# TakpadV3.net
KiCad netlist of a schematic drawn in EAGLE
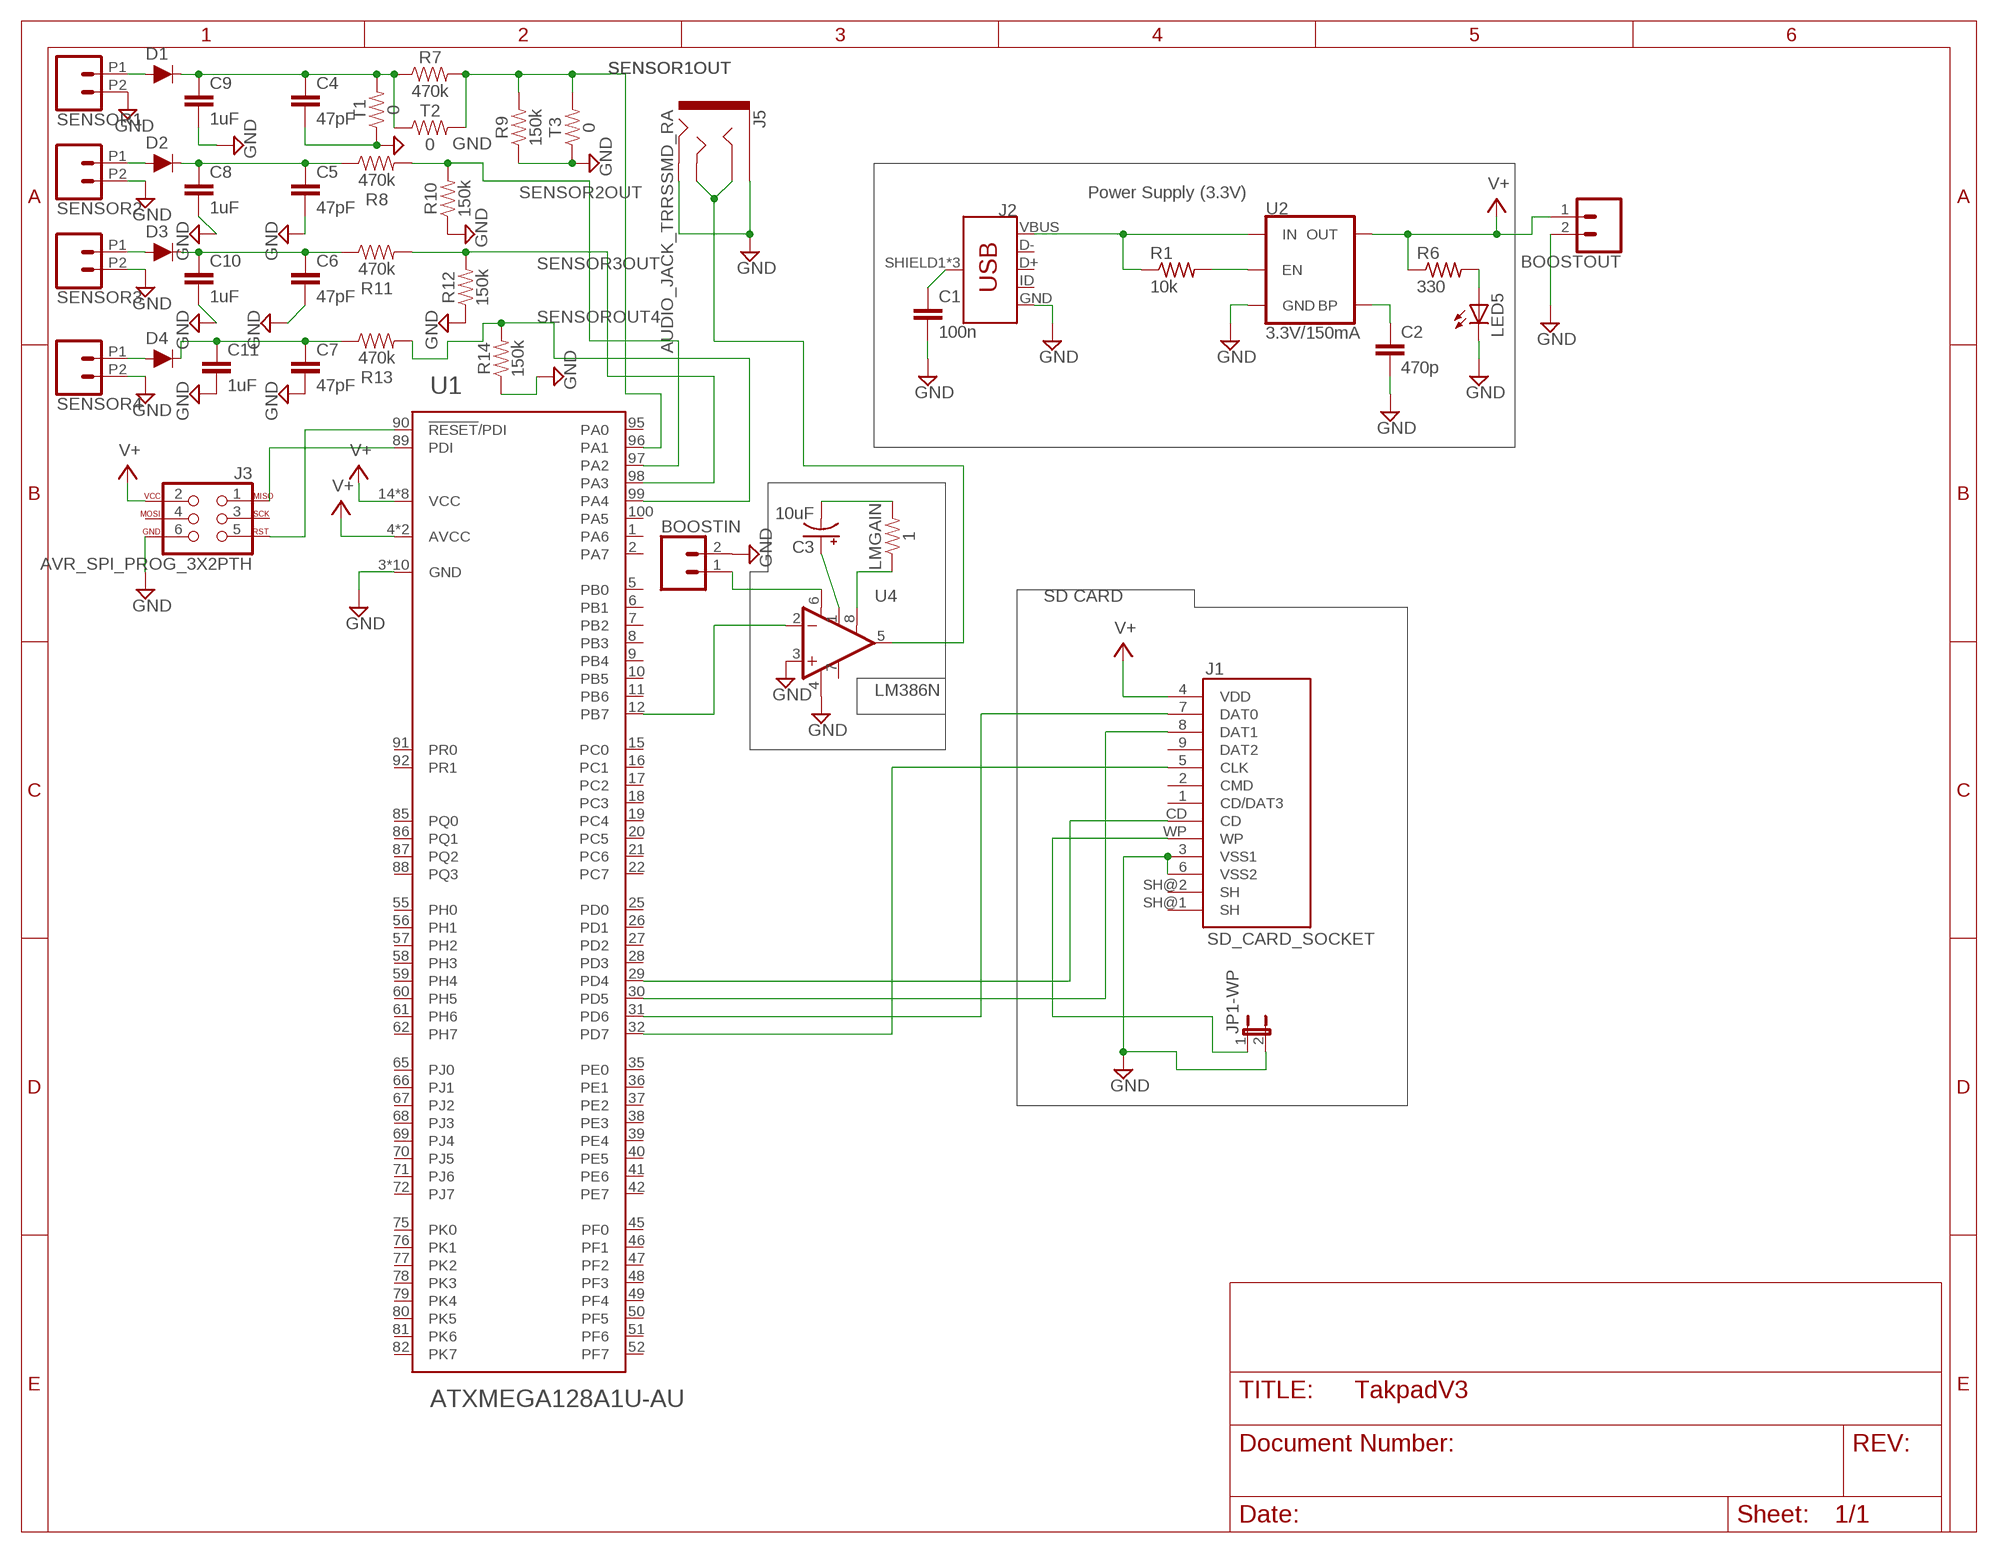
[diagram p0: schematic, sheet 1]

(export (version "E")
  (design (tool "Eeschema 10.0.6"))
  (components
    (comp (ref "BOOSTIN")
      (value "CONN_02")
      (footprint "eagle-import:1X02")
      (libsource (lib "eagle-import") (part "CONN_02"))
    )
    (comp (ref "BOOSTOUT")
      (value "CONN_02")
      (footprint "eagle-import:1X02")
      (libsource (lib "eagle-import") (part "CONN_02"))
    )
    (comp (ref "C1")
      (value "100n")
      (footprint "eagle-import:C1206")
      (libsource (lib "eagle-import") (part "C-EUC1206"))
    )
    (comp (ref "C2")
      (value "470p")
      (footprint "eagle-import:C1206")
      (libsource (lib "eagle-import") (part "C-EUC1206"))
    )
    (comp (ref "C3")
      (value "10uF")
      (footprint "eagle-import:CPOL-RADIAL-2.5MM-5MM-KIT")
      (libsource (lib "eagle-import") (part "10UF-POLAR-RADIAL-2.5MM-KIT-25V-20%"))
    )
    (comp (ref "C4")
      (value "47pF")
      (footprint "eagle-import:0603")
      (libsource (lib "eagle-import") (part "47PF-0603-50V-5%"))
    )
    (comp (ref "C5")
      (value "47pF")
      (footprint "eagle-import:0603")
      (libsource (lib "eagle-import") (part "47PF-0603-50V-5%"))
    )
    (comp (ref "C6")
      (value "47pF")
      (footprint "eagle-import:0603")
      (libsource (lib "eagle-import") (part "47PF-0603-50V-5%"))
    )
    (comp (ref "C7")
      (value "47pF")
      (footprint "eagle-import:0603")
      (libsource (lib "eagle-import") (part "47PF-0603-50V-5%"))
    )
    (comp (ref "C8")
      (value "1uF")
      (footprint "eagle-import:0603")
      (libsource (lib "eagle-import") (part "47PF-0603-50V-5%"))
    )
    (comp (ref "C9")
      (value "1uF")
      (footprint "eagle-import:0603")
      (libsource (lib "eagle-import") (part "47PF-0603-50V-5%"))
    )
    (comp (ref "C10")
      (value "1uF")
      (footprint "eagle-import:0603")
      (libsource (lib "eagle-import") (part "47PF-0603-50V-5%"))
    )
    (comp (ref "C11")
      (value "1uF")
      (footprint "eagle-import:0603")
      (libsource (lib "eagle-import") (part "47PF-0603-50V-5%"))
    )
    (comp (ref "D1")
      (value "200mA/100V/1V")
      (footprint "eagle-import:DIODE-1N4148")
      (libsource (lib "eagle-import") (part "DIODE-1N4148"))
    )
    (comp (ref "D2")
      (value "200mA/100V/1V")
      (footprint "eagle-import:DIODE-1N4148")
      (libsource (lib "eagle-import") (part "DIODE-1N4148"))
    )
    (comp (ref "D3")
      (value "200mA/100V/1V")
      (footprint "eagle-import:DIODE-1N4148")
      (libsource (lib "eagle-import") (part "DIODE-1N4148"))
    )
    (comp (ref "D4")
      (value "200mA/100V/1V")
      (footprint "eagle-import:DIODE-1N4148")
      (libsource (lib "eagle-import") (part "DIODE-1N4148"))
    )
    (comp (ref "J1")
      (value "SD_CARD_SOCKET")
      (footprint "eagle-import:SD")
      (libsource (lib "eagle-import") (part "SD_CARD_SOCKET"))
    )
    (comp (ref "J2")
      (value "USB_MICRO-B_FEMALE-SMT")
      (footprint "eagle-import:USB-B-MICRO-SMD")
      (libsource (lib "eagle-import") (part "USB_MICRO-B_FEMALE-SMT"))
    )
    (comp (ref "J3")
      (value "AVR_SPI_PROG_3X2PTH")
      (footprint "eagle-import:2X3")
      (libsource (lib "eagle-import") (part "AVR_SPI_PROG_3X2PTH"))
    )
    (comp (ref "J5")
      (value "AUDIO_JACK_TRRSSMD_RA")
      (footprint "eagle-import:AUDIO_JACK_3.5MM_TRRS_SMD_RA")
      (fields (field (name "SPICEPREFIX") "E"))
      (libsource (lib "eagle-import") (part "AUDIO_JACK_TRRSSMD_RA"))
    )
    (comp (ref "JP1-WP")
      (value "JUMPER-2PTH")
      (footprint "eagle-import:1X02")
      (libsource (lib "eagle-import") (part "JUMPER-2PTH"))
    )
    (comp (ref "LED5")
      (value "LED10MM")
      (footprint "eagle-import:LED10MM")
      (libsource (lib "eagle-import") (part "LED10MM"))
    )
    (comp (ref "LMGAIN")
      (value "1")
      (footprint "eagle-import:0603")
      (libsource (lib "eagle-import") (part "1OHM-0603-1/10W-1%"))
    )
    (comp (ref "R1")
      (value "10k")
      (footprint "eagle-import:M1206")
      (libsource (lib "eagle-import") (part "R-US_M1206"))
    )
    (comp (ref "R6")
      (value "330")
      (footprint "eagle-import:0204_7")
      (libsource (lib "eagle-import") (part "R-US_0204/7"))
    )
    (comp (ref "R7")
      (value "470k")
      (footprint "eagle-import:AXIAL-0.3")
      (libsource (lib "eagle-import") (part "1KOHM-HORIZ-1/4W-1%"))
    )
    (comp (ref "R8")
      (value "470k")
      (footprint "eagle-import:AXIAL-0.3")
      (libsource (lib "eagle-import") (part "1KOHM-HORIZ-1/4W-1%"))
    )
    (comp (ref "R9")
      (value "150k")
      (footprint "eagle-import:AXIAL-0.3")
      (libsource (lib "eagle-import") (part "1KOHM-HORIZ-1/4W-1%"))
    )
    (comp (ref "R10")
      (value "150k")
      (footprint "eagle-import:AXIAL-0.3")
      (libsource (lib "eagle-import") (part "1KOHM-HORIZ-1/4W-1%"))
    )
    (comp (ref "R11")
      (value "470k")
      (footprint "eagle-import:AXIAL-0.3")
      (libsource (lib "eagle-import") (part "1KOHM-HORIZ-1/4W-1%"))
    )
    (comp (ref "R12")
      (value "150k")
      (footprint "eagle-import:AXIAL-0.3")
      (libsource (lib "eagle-import") (part "1KOHM-HORIZ-1/4W-1%"))
    )
    (comp (ref "R13")
      (value "470k")
      (footprint "eagle-import:AXIAL-0.3")
      (libsource (lib "eagle-import") (part "1KOHM-HORIZ-1/4W-1%"))
    )
    (comp (ref "R14")
      (value "150k")
      (footprint "eagle-import:AXIAL-0.3")
      (libsource (lib "eagle-import") (part "1KOHM-HORIZ-1/4W-1%"))
    )
    (comp (ref "SENSOR1")
      (value "CONN_022.54MM_SCREWTERM")
      (footprint "eagle-import:1X02_2.54_SCREWTERM")
      (libsource (lib "eagle-import") (part "CONN_022.54MM_SCREWTERM"))
    )
    (comp (ref "SENSOR2")
      (value "CONN_022.54MM_SCREWTERM")
      (footprint "eagle-import:1X02_2.54_SCREWTERM")
      (libsource (lib "eagle-import") (part "CONN_022.54MM_SCREWTERM"))
    )
    (comp (ref "SENSOR3")
      (value "CONN_022.54MM_SCREWTERM")
      (footprint "eagle-import:1X02_2.54_SCREWTERM")
      (libsource (lib "eagle-import") (part "CONN_022.54MM_SCREWTERM"))
    )
    (comp (ref "SENSOR4")
      (value "CONN_022.54MM_SCREWTERM")
      (footprint "eagle-import:1X02_2.54_SCREWTERM")
      (libsource (lib "eagle-import") (part "CONN_022.54MM_SCREWTERM"))
    )
    (comp (ref "T1")
      (value "0")
      (footprint "eagle-import:AXIAL-0.3")
      (libsource (lib "eagle-import") (part "1KOHM-HORIZ-1/4W-1%"))
    )
    (comp (ref "T2")
      (value "0")
      (footprint "eagle-import:AXIAL-0.3")
      (libsource (lib "eagle-import") (part "1KOHM-HORIZ-1/4W-1%"))
    )
    (comp (ref "T3")
      (value "0")
      (footprint "eagle-import:AXIAL-0.3")
      (libsource (lib "eagle-import") (part "1KOHM-HORIZ-1/4W-1%"))
    )
    (comp (ref "U1")
      (value "ATXMEGA128A1U-AU")
      (footprint "eagle-import:TQFP-100A-100")
      (libsource (lib "eagle-import") (part "ATXMEGA128A1U-AU"))
    )
    (comp (ref "U2")
      (value "3.3V/150mA")
      (footprint "eagle-import:SOT23-5")
      (libsource (lib "eagle-import") (part "V_REG_MIC52053.3V"))
    )
    (comp (ref "U4")
      (value "LM386N")
      (footprint "eagle-import:DIP08")
      (libsource (lib "eagle-import") (part "LM386"))
    )
  )
  (nets
    (net (code "1") (name "/SENSOR1OUT") (class "Default")
      (node (ref "R7") (pin "P$2") (pinfunction "2_P$2") (pintype "passive"))
      (node (ref "R9") (pin "P$2") (pinfunction "2_P$2") (pintype "passive"))
      (node (ref "T2") (pin "P$2") (pinfunction "2_P$2") (pintype "passive"))
      (node (ref "T3") (pin "P$2") (pinfunction "2_P$2") (pintype "passive"))
      (node (ref "U1") (pin "96") (pinfunction "PA1_96") (pintype "bidirectional"))
    )
    (net (code "2") (name "/SENSOR2OUT") (class "Default")
      (node (ref "R10") (pin "P$2") (pinfunction "2_P$2") (pintype "passive"))
      (node (ref "R8") (pin "P$2") (pinfunction "2_P$2") (pintype "passive"))
      (node (ref "U1") (pin "97") (pinfunction "PA2_97") (pintype "bidirectional"))
    )
    (net (code "3") (name "/SENSOR3OUT") (class "Default")
      (node (ref "R11") (pin "P$2") (pinfunction "2_P$2") (pintype "passive"))
      (node (ref "R12") (pin "P$2") (pinfunction "2_P$2") (pintype "passive"))
      (node (ref "U1") (pin "98") (pinfunction "PA3_98") (pintype "bidirectional"))
    )
    (net (code "4") (name "/SENSOROUT4") (class "Default")
      (node (ref "R13") (pin "P$2") (pinfunction "2_P$2") (pintype "passive"))
      (node (ref "R14") (pin "P$2") (pinfunction "2_P$2") (pintype "passive"))
      (node (ref "U1") (pin "99") (pinfunction "PA4_99") (pintype "bidirectional"))
    )
    (net (code "5") (name "GND") (class "Default")
      (node (ref "BOOSTIN") (pin "2") (pinfunction "2_2") (pintype "passive"))
      (node (ref "BOOSTOUT") (pin "2") (pinfunction "2_2") (pintype "passive"))
      (node (ref "C1") (pin "2") (pinfunction "2_2") (pintype "passive"))
      (node (ref "C10") (pin "2") (pinfunction "2_2") (pintype "passive"))
      (node (ref "C11") (pin "2") (pinfunction "2_2") (pintype "passive"))
      (node (ref "C2") (pin "2") (pinfunction "2_2") (pintype "passive"))
      (node (ref "C4") (pin "2") (pinfunction "2_2") (pintype "passive"))
      (node (ref "C5") (pin "2") (pinfunction "2_2") (pintype "passive"))
      (node (ref "C6") (pin "2") (pinfunction "2_2") (pintype "passive"))
      (node (ref "C7") (pin "2") (pinfunction "2_2") (pintype "passive"))
      (node (ref "C8") (pin "2") (pinfunction "2_2") (pintype "passive"))
      (node (ref "C9") (pin "2") (pinfunction "2_2") (pintype "passive"))
      (node (ref "J1") (pin "3") (pinfunction "VSS1_3") (pintype "power_in"))
      (node (ref "J1") (pin "6") (pinfunction "VSS2_6") (pintype "power_in"))
      (node (ref "J2") (pin "GND") (pinfunction "GND_GND") (pintype "power_in"))
      (node (ref "J3") (pin "6") (pinfunction "6_6") (pintype "passive"))
      (node (ref "J5") (pin "EARTH") (pinfunction "EARTH_EARTH") (pintype "bidirectional"))
      (node (ref "J5") (pin "RING2") (pinfunction "RING2_RING2") (pintype "bidirectional"))
      (node (ref "JP1-WP") (pin "2") (pinfunction "2_2") (pintype "passive"))
      (node (ref "LED5") (pin "K") (pinfunction "C_K") (pintype "passive"))
      (node (ref "R10") (pin "P$1") (pinfunction "1_P$1") (pintype "passive"))
      (node (ref "R12") (pin "P$1") (pinfunction "1_P$1") (pintype "passive"))
      (node (ref "R14") (pin "P$1") (pinfunction "1_P$1") (pintype "passive"))
      (node (ref "R9") (pin "P$1") (pinfunction "1_P$1") (pintype "passive"))
      (node (ref "SENSOR1") (pin "P2") (pinfunction "2_P2") (pintype "passive"))
      (node (ref "SENSOR2") (pin "P2") (pinfunction "2_P2") (pintype "passive"))
      (node (ref "SENSOR3") (pin "P2") (pinfunction "2_P2") (pintype "passive"))
      (node (ref "SENSOR4") (pin "P2") (pinfunction "2_P2") (pintype "passive"))
      (node (ref "T1") (pin "P$1") (pinfunction "1_P$1") (pintype "passive"))
      (node (ref "T3") (pin "P$1") (pinfunction "1_P$1") (pintype "passive"))
      (node (ref "U1") (pin "13") (pinfunction "GND_13") (pintype "power_in"))
      (node (ref "U1") (pin "23") (pinfunction "GND_23") (pintype "power_in"))
      (node (ref "U1") (pin "3") (pinfunction "GND_3") (pintype "power_in"))
      (node (ref "U1") (pin "33") (pinfunction "GND_33") (pintype "power_in"))
      (node (ref "U1") (pin "43") (pinfunction "GND_43") (pintype "power_in"))
      (node (ref "U1") (pin "53") (pinfunction "GND_53") (pintype "power_in"))
      (node (ref "U1") (pin "63") (pinfunction "GND_63") (pintype "power_in"))
      (node (ref "U1") (pin "73") (pinfunction "GND_73") (pintype "power_in"))
      (node (ref "U1") (pin "84") (pinfunction "GND_84") (pintype "power_in"))
      (node (ref "U1") (pin "93") (pinfunction "GND_93") (pintype "power_in"))
      (node (ref "U2") (pin "2") (pinfunction "GND_2") (pintype "input"))
      (node (ref "U4") (pin "3") (pinfunction "+IN_3") (pintype "input"))
      (node (ref "U4") (pin "4") (pinfunction "V-_4") (pintype "power_in"))
    )
    (net (code "6") (name "Net-(C1-Pad1)") (class "Default")
      (node (ref "C1") (pin "1") (pinfunction "1_1") (pintype "passive"))
      (node (ref "J2") (pin "SHIELD1") (pinfunction "SHIELD_SHIELD1") (pintype "bidirectional"))
      (node (ref "J2") (pin "SHIELD2") (pinfunction "SHIELD_SHIELD2") (pintype "bidirectional"))
      (node (ref "J2") (pin "SHIELD3") (pinfunction "SHIELD_SHIELD3") (pintype "bidirectional"))
    )
    (net (code "7") (name "Net-(C3-+)") (class "Default")
      (node (ref "C3") (pin "1") (pinfunction "+_1") (pintype "passive"))
      (node (ref "U4") (pin "1") (pinfunction "GAIN_1") (pintype "bidirectional"))
    )
    (net (code "8") (name "Net-(C3--)") (class "Default")
      (node (ref "C3") (pin "2") (pinfunction "-_2") (pintype "passive"))
      (node (ref "LMGAIN") (pin "2") (pinfunction "2_2") (pintype "passive"))
    )
    (net (code "9") (name "Net-(J1-CLK)") (class "Default")
      (node (ref "J1") (pin "5") (pinfunction "CLK_5") (pintype "bidirectional"))
      (node (ref "U1") (pin "32") (pinfunction "PD7_32") (pintype "bidirectional"))
    )
    (net (code "10") (name "Net-(J1-DAT0)") (class "Default")
      (node (ref "J1") (pin "7") (pinfunction "DAT0_7") (pintype "bidirectional"))
      (node (ref "U1") (pin "31") (pinfunction "PD6_31") (pintype "bidirectional"))
    )
    (net (code "11") (name "Net-(J1-DAT1)") (class "Default")
      (node (ref "J1") (pin "8") (pinfunction "DAT1_8") (pintype "bidirectional"))
      (node (ref "U1") (pin "30") (pinfunction "PD5_30") (pintype "bidirectional"))
    )
    (net (code "12") (name "Net-(J1-PadWP)") (class "Default")
      (node (ref "J1") (pin "WP") (pinfunction "WP_WP") (pintype "bidirectional"))
      (node (ref "JP1-WP") (pin "1") (pinfunction "1_1") (pintype "passive"))
    )
    (net (code "13") (name "Net-(LED5-PadA)") (class "Default")
      (node (ref "LED5") (pin "A") (pinfunction "A_A") (pintype "passive"))
      (node (ref "R6") (pin "2") (pinfunction "2_2") (pintype "passive"))
    )
    (net (code "14") (name "Net-(LMGAIN-Pad1)") (class "Default")
      (node (ref "LMGAIN") (pin "1") (pinfunction "1_1") (pintype "passive"))
      (node (ref "U4") (pin "8") (pinfunction "GAIN_8") (pintype "bidirectional"))
    )
    (net (code "15") (name "Net-(R7-1)") (class "Default")
      (node (ref "C4") (pin "1") (pinfunction "1_1") (pintype "passive"))
      (node (ref "C9") (pin "1") (pinfunction "1_1") (pintype "passive"))
      (node (ref "D1") (pin "C") (pinfunction "C_C") (pintype "passive"))
      (node (ref "R7") (pin "P$1") (pinfunction "1_P$1") (pintype "passive"))
      (node (ref "T1") (pin "P$2") (pinfunction "2_P$2") (pintype "passive"))
      (node (ref "T2") (pin "P$1") (pinfunction "1_P$1") (pintype "passive"))
    )
    (net (code "16") (name "Net-(R8-1)") (class "Default")
      (node (ref "C5") (pin "1") (pinfunction "1_1") (pintype "passive"))
      (node (ref "C8") (pin "1") (pinfunction "1_1") (pintype "passive"))
      (node (ref "D2") (pin "C") (pinfunction "C_C") (pintype "passive"))
      (node (ref "R8") (pin "P$1") (pinfunction "1_P$1") (pintype "passive"))
    )
    (net (code "17") (name "Net-(R11-1)") (class "Default")
      (node (ref "C10") (pin "1") (pinfunction "1_1") (pintype "passive"))
      (node (ref "C6") (pin "1") (pinfunction "1_1") (pintype "passive"))
      (node (ref "D3") (pin "C") (pinfunction "C_C") (pintype "passive"))
      (node (ref "R11") (pin "P$1") (pinfunction "1_P$1") (pintype "passive"))
    )
    (net (code "18") (name "Net-(R13-1)") (class "Default")
      (node (ref "C11") (pin "1") (pinfunction "1_1") (pintype "passive"))
      (node (ref "C7") (pin "1") (pinfunction "1_1") (pintype "passive"))
      (node (ref "D4") (pin "C") (pinfunction "C_C") (pintype "passive"))
      (node (ref "R13") (pin "P$1") (pinfunction "1_P$1") (pintype "passive"))
    )
    (net (code "19") (name "Net-(SENSOR1-1)") (class "Default")
      (node (ref "D1") (pin "A") (pinfunction "A_A") (pintype "passive"))
      (node (ref "SENSOR1") (pin "P1") (pinfunction "1_P1") (pintype "passive"))
    )
    (net (code "20") (name "Net-(SENSOR2-1)") (class "Default")
      (node (ref "D2") (pin "A") (pinfunction "A_A") (pintype "passive"))
      (node (ref "SENSOR2") (pin "P1") (pinfunction "1_P1") (pintype "passive"))
    )
    (net (code "21") (name "Net-(SENSOR3-1)") (class "Default")
      (node (ref "D3") (pin "A") (pinfunction "A_A") (pintype "passive"))
      (node (ref "SENSOR3") (pin "P1") (pinfunction "1_P1") (pintype "passive"))
    )
    (net (code "22") (name "Net-(SENSOR4-1)") (class "Default")
      (node (ref "D4") (pin "A") (pinfunction "A_A") (pintype "passive"))
      (node (ref "SENSOR4") (pin "P1") (pinfunction "1_P1") (pintype "passive"))
    )
    (net (code "23") (name "Net-(U1-PB7)") (class "Default")
      (node (ref "U1") (pin "12") (pinfunction "PB7_12") (pintype "bidirectional"))
      (node (ref "U4") (pin "2") (pinfunction "-IN_2") (pintype "input"))
    )
    (net (code "24") (name "Net-(U1-PD4)") (class "Default")
      (node (ref "J1") (pin "CD") (pinfunction "CD_CD") (pintype "bidirectional"))
      (node (ref "U1") (pin "29") (pinfunction "PD4_29") (pintype "bidirectional"))
    )
    (net (code "25") (name "Net-(U1-PDI)") (class "Default")
      (node (ref "J3") (pin "1") (pinfunction "1_1") (pintype "passive"))
      (node (ref "U1") (pin "89") (pinfunction "PDI_89") (pintype "bidirectional"))
    )
    (net (code "26") (name "Net-(U1-~{RESET}{slash}PDI)") (class "Default")
      (node (ref "J3") (pin "5") (pinfunction "5_5") (pintype "passive"))
      (node (ref "U1") (pin "90") (pinfunction "~{RESET}/PDI_90") (pintype "bidirectional"))
    )
    (net (code "27") (name "Net-(U2-BP)") (class "Default")
      (node (ref "C2") (pin "1") (pinfunction "1_1") (pintype "passive"))
      (node (ref "U2") (pin "4") (pinfunction "BP_4") (pintype "input"))
    )
    (net (code "28") (name "Net-(U2-EN)") (class "Default")
      (node (ref "R1") (pin "2") (pinfunction "2_2") (pintype "passive"))
      (node (ref "U2") (pin "3") (pinfunction "EN_3") (pintype "input"))
    )
    (net (code "29") (name "Net-(U2-IN)") (class "Default")
      (node (ref "J2") (pin "VBUS") (pinfunction "VBUS_VBUS") (pintype "power_in"))
      (node (ref "R1") (pin "1") (pinfunction "1_1") (pintype "passive"))
      (node (ref "U2") (pin "1") (pinfunction "IN_1") (pintype "input"))
    )
    (net (code "30") (name "Net-(U4-OUT)") (class "Default")
      (node (ref "J5") (pin "RING1") (pinfunction "RING1_RING1") (pintype "bidirectional"))
      (node (ref "J5") (pin "TIP") (pinfunction "TIP_TIP") (pintype "bidirectional"))
      (node (ref "U4") (pin "5") (pinfunction "OUT_5") (pintype "output"))
    )
    (net (code "31") (name "Net-(U4-V+)") (class "Default")
      (node (ref "BOOSTIN") (pin "1") (pinfunction "1_1") (pintype "passive"))
      (node (ref "U4") (pin "6") (pinfunction "V+_6") (pintype "power_in"))
    )
    (net (code "32") (name "V+") (class "Default")
      (node (ref "BOOSTOUT") (pin "1") (pinfunction "1_1") (pintype "passive"))
      (node (ref "J1") (pin "4") (pinfunction "VDD_4") (pintype "power_in"))
      (node (ref "J3") (pin "2") (pinfunction "2_2") (pintype "passive"))
      (node (ref "R6") (pin "1") (pinfunction "1_1") (pintype "passive"))
      (node (ref "U1") (pin "14") (pinfunction "VCC_14") (pintype "power_in"))
      (node (ref "U1") (pin "24") (pinfunction "VCC_24") (pintype "power_in"))
      (node (ref "U1") (pin "34") (pinfunction "VCC_34") (pintype "power_in"))
      (node (ref "U1") (pin "4") (pinfunction "AVCC_4") (pintype "power_in"))
      (node (ref "U1") (pin "44") (pinfunction "VCC_44") (pintype "power_in"))
      (node (ref "U1") (pin "54") (pinfunction "VCC_54") (pintype "power_in"))
      (node (ref "U1") (pin "64") (pinfunction "VCC_64") (pintype "power_in"))
      (node (ref "U1") (pin "74") (pinfunction "VCC_74") (pintype "power_in"))
      (node (ref "U1") (pin "83") (pinfunction "VCC_83") (pintype "power_in"))
      (node (ref "U1") (pin "94") (pinfunction "AVCC_94") (pintype "power_in"))
      (node (ref "U2") (pin "5") (pinfunction "OUT_5") (pintype "passive"))
    )
    (net (code "33") (name "unconnected-(J1-CD{slash}DAT3-Pad1)") (class "Default")
      (node (ref "J1") (pin "1") (pinfunction "CD/DAT3_1") (pintype "bidirectional"))
    )
    (net (code "34") (name "unconnected-(J1-CMD-Pad2)") (class "Default")
      (node (ref "J1") (pin "2") (pinfunction "CMD_2") (pintype "bidirectional"))
    )
    (net (code "35") (name "unconnected-(J1-DAT2-Pad9)") (class "Default")
      (node (ref "J1") (pin "9") (pinfunction "DAT2_9") (pintype "bidirectional"))
    )
    (net (code "36") (name "unconnected-(J1-SH-PadSH@1)") (class "Default")
      (node (ref "J1") (pin "SH@1") (pinfunction "SH_SH@1") (pintype "bidirectional"))
    )
    (net (code "37") (name "unconnected-(J1-SH-PadSH@2)") (class "Default")
      (node (ref "J1") (pin "SH@2") (pinfunction "SH_SH@2") (pintype "bidirectional"))
    )
    (net (code "38") (name "unconnected-(J2-PadD+)") (class "Default")
      (node (ref "J2") (pin "D+") (pinfunction "D+_D+") (pintype "bidirectional"))
    )
    (net (code "39") (name "unconnected-(J2-PadD-)") (class "Default")
      (node (ref "J2") (pin "D-") (pinfunction "D-_D-") (pintype "bidirectional"))
    )
    (net (code "40") (name "unconnected-(J2-PadID)") (class "Default")
      (node (ref "J2") (pin "ID") (pinfunction "ID_ID") (pintype "bidirectional"))
    )
    (net (code "41") (name "unconnected-(J3-Pad3)") (class "Default")
      (node (ref "J3") (pin "3") (pinfunction "3_3") (pintype "passive"))
    )
    (net (code "42") (name "unconnected-(J3-Pad4)") (class "Default")
      (node (ref "J3") (pin "4") (pinfunction "4_4") (pintype "passive"))
    )
    (net (code "43") (name "unconnected-(U1-PA0-Pad95)") (class "Default")
      (node (ref "U1") (pin "95") (pinfunction "PA0_95") (pintype "bidirectional"))
    )
    (net (code "44") (name "unconnected-(U1-PA5-Pad100)") (class "Default")
      (node (ref "U1") (pin "100") (pinfunction "PA5_100") (pintype "bidirectional"))
    )
    (net (code "45") (name "unconnected-(U1-PA6-Pad1)") (class "Default")
      (node (ref "U1") (pin "1") (pinfunction "PA6_1") (pintype "bidirectional"))
    )
    (net (code "46") (name "unconnected-(U1-PA7-Pad2)") (class "Default")
      (node (ref "U1") (pin "2") (pinfunction "PA7_2") (pintype "bidirectional"))
    )
    (net (code "47") (name "unconnected-(U1-PB0-Pad5)") (class "Default")
      (node (ref "U1") (pin "5") (pinfunction "PB0_5") (pintype "bidirectional"))
    )
    (net (code "48") (name "unconnected-(U1-PB1-Pad6)") (class "Default")
      (node (ref "U1") (pin "6") (pinfunction "PB1_6") (pintype "bidirectional"))
    )
    (net (code "49") (name "unconnected-(U1-PB2-Pad7)") (class "Default")
      (node (ref "U1") (pin "7") (pinfunction "PB2_7") (pintype "bidirectional"))
    )
    (net (code "50") (name "unconnected-(U1-PB3-Pad8)") (class "Default")
      (node (ref "U1") (pin "8") (pinfunction "PB3_8") (pintype "bidirectional"))
    )
    (net (code "51") (name "unconnected-(U1-PB4-Pad9)") (class "Default")
      (node (ref "U1") (pin "9") (pinfunction "PB4_9") (pintype "bidirectional"))
    )
    (net (code "52") (name "unconnected-(U1-PB5-Pad10)") (class "Default")
      (node (ref "U1") (pin "10") (pinfunction "PB5_10") (pintype "bidirectional"))
    )
    (net (code "53") (name "unconnected-(U1-PB6-Pad11)") (class "Default")
      (node (ref "U1") (pin "11") (pinfunction "PB6_11") (pintype "bidirectional"))
    )
    (net (code "54") (name "unconnected-(U1-PC0-Pad15)") (class "Default")
      (node (ref "U1") (pin "15") (pinfunction "PC0_15") (pintype "bidirectional"))
    )
    (net (code "55") (name "unconnected-(U1-PC1-Pad16)") (class "Default")
      (node (ref "U1") (pin "16") (pinfunction "PC1_16") (pintype "bidirectional"))
    )
    (net (code "56") (name "unconnected-(U1-PC2-Pad17)") (class "Default")
      (node (ref "U1") (pin "17") (pinfunction "PC2_17") (pintype "bidirectional"))
    )
    (net (code "57") (name "unconnected-(U1-PC3-Pad18)") (class "Default")
      (node (ref "U1") (pin "18") (pinfunction "PC3_18") (pintype "bidirectional"))
    )
    (net (code "58") (name "unconnected-(U1-PC4-Pad19)") (class "Default")
      (node (ref "U1") (pin "19") (pinfunction "PC4_19") (pintype "bidirectional"))
    )
    (net (code "59") (name "unconnected-(U1-PC5-Pad20)") (class "Default")
      (node (ref "U1") (pin "20") (pinfunction "PC5_20") (pintype "bidirectional"))
    )
    (net (code "60") (name "unconnected-(U1-PC6-Pad21)") (class "Default")
      (node (ref "U1") (pin "21") (pinfunction "PC6_21") (pintype "bidirectional"))
    )
    (net (code "61") (name "unconnected-(U1-PC7-Pad22)") (class "Default")
      (node (ref "U1") (pin "22") (pinfunction "PC7_22") (pintype "bidirectional"))
    )
    (net (code "62") (name "unconnected-(U1-PD0-Pad25)") (class "Default")
      (node (ref "U1") (pin "25") (pinfunction "PD0_25") (pintype "bidirectional"))
    )
    (net (code "63") (name "unconnected-(U1-PD1-Pad26)") (class "Default")
      (node (ref "U1") (pin "26") (pinfunction "PD1_26") (pintype "bidirectional"))
    )
    (net (code "64") (name "unconnected-(U1-PD2-Pad27)") (class "Default")
      (node (ref "U1") (pin "27") (pinfunction "PD2_27") (pintype "bidirectional"))
    )
    (net (code "65") (name "unconnected-(U1-PD3-Pad28)") (class "Default")
      (node (ref "U1") (pin "28") (pinfunction "PD3_28") (pintype "bidirectional"))
    )
    (net (code "66") (name "unconnected-(U1-PE0-Pad35)") (class "Default")
      (node (ref "U1") (pin "35") (pinfunction "PE0_35") (pintype "bidirectional"))
    )
    (net (code "67") (name "unconnected-(U1-PE1-Pad36)") (class "Default")
      (node (ref "U1") (pin "36") (pinfunction "PE1_36") (pintype "bidirectional"))
    )
    (net (code "68") (name "unconnected-(U1-PE2-Pad37)") (class "Default")
      (node (ref "U1") (pin "37") (pinfunction "PE2_37") (pintype "bidirectional"))
    )
    (net (code "69") (name "unconnected-(U1-PE3-Pad38)") (class "Default")
      (node (ref "U1") (pin "38") (pinfunction "PE3_38") (pintype "bidirectional"))
    )
    (net (code "70") (name "unconnected-(U1-PE4-Pad39)") (class "Default")
      (node (ref "U1") (pin "39") (pinfunction "PE4_39") (pintype "bidirectional"))
    )
    (net (code "71") (name "unconnected-(U1-PE5-Pad40)") (class "Default")
      (node (ref "U1") (pin "40") (pinfunction "PE5_40") (pintype "bidirectional"))
    )
    (net (code "72") (name "unconnected-(U1-PE6-Pad41)") (class "Default")
      (node (ref "U1") (pin "41") (pinfunction "PE6_41") (pintype "bidirectional"))
    )
    (net (code "73") (name "unconnected-(U1-PE7-Pad42)") (class "Default")
      (node (ref "U1") (pin "42") (pinfunction "PE7_42") (pintype "bidirectional"))
    )
    (net (code "74") (name "unconnected-(U1-PF0-Pad45)") (class "Default")
      (node (ref "U1") (pin "45") (pinfunction "PF0_45") (pintype "bidirectional"))
    )
    (net (code "75") (name "unconnected-(U1-PF1-Pad46)") (class "Default")
      (node (ref "U1") (pin "46") (pinfunction "PF1_46") (pintype "bidirectional"))
    )
    (net (code "76") (name "unconnected-(U1-PF2-Pad47)") (class "Default")
      (node (ref "U1") (pin "47") (pinfunction "PF2_47") (pintype "bidirectional"))
    )
    (net (code "77") (name "unconnected-(U1-PF3-Pad48)") (class "Default")
      (node (ref "U1") (pin "48") (pinfunction "PF3_48") (pintype "bidirectional"))
    )
    (net (code "78") (name "unconnected-(U1-PF4-Pad49)") (class "Default")
      (node (ref "U1") (pin "49") (pinfunction "PF4_49") (pintype "bidirectional"))
    )
    (net (code "79") (name "unconnected-(U1-PF5-Pad50)") (class "Default")
      (node (ref "U1") (pin "50") (pinfunction "PF5_50") (pintype "bidirectional"))
    )
    (net (code "80") (name "unconnected-(U1-PF6-Pad51)") (class "Default")
      (node (ref "U1") (pin "51") (pinfunction "PF6_51") (pintype "bidirectional"))
    )
    (net (code "81") (name "unconnected-(U1-PF7-Pad52)") (class "Default")
      (node (ref "U1") (pin "52") (pinfunction "PF7_52") (pintype "bidirectional"))
    )
    (net (code "82") (name "unconnected-(U1-PH0-Pad55)") (class "Default")
      (node (ref "U1") (pin "55") (pinfunction "PH0_55") (pintype "bidirectional"))
    )
    (net (code "83") (name "unconnected-(U1-PH1-Pad56)") (class "Default")
      (node (ref "U1") (pin "56") (pinfunction "PH1_56") (pintype "bidirectional"))
    )
    (net (code "84") (name "unconnected-(U1-PH2-Pad57)") (class "Default")
      (node (ref "U1") (pin "57") (pinfunction "PH2_57") (pintype "bidirectional"))
    )
    (net (code "85") (name "unconnected-(U1-PH3-Pad58)") (class "Default")
      (node (ref "U1") (pin "58") (pinfunction "PH3_58") (pintype "bidirectional"))
    )
    (net (code "86") (name "unconnected-(U1-PH4-Pad59)") (class "Default")
      (node (ref "U1") (pin "59") (pinfunction "PH4_59") (pintype "bidirectional"))
    )
    (net (code "87") (name "unconnected-(U1-PH5-Pad60)") (class "Default")
      (node (ref "U1") (pin "60") (pinfunction "PH5_60") (pintype "bidirectional"))
    )
    (net (code "88") (name "unconnected-(U1-PH6-Pad61)") (class "Default")
      (node (ref "U1") (pin "61") (pinfunction "PH6_61") (pintype "bidirectional"))
    )
    (net (code "89") (name "unconnected-(U1-PH7-Pad62)") (class "Default")
      (node (ref "U1") (pin "62") (pinfunction "PH7_62") (pintype "bidirectional"))
    )
    (net (code "90") (name "unconnected-(U1-PJ0-Pad65)") (class "Default")
      (node (ref "U1") (pin "65") (pinfunction "PJ0_65") (pintype "bidirectional"))
    )
    (net (code "91") (name "unconnected-(U1-PJ1-Pad66)") (class "Default")
      (node (ref "U1") (pin "66") (pinfunction "PJ1_66") (pintype "bidirectional"))
    )
    (net (code "92") (name "unconnected-(U1-PJ2-Pad67)") (class "Default")
      (node (ref "U1") (pin "67") (pinfunction "PJ2_67") (pintype "bidirectional"))
    )
    (net (code "93") (name "unconnected-(U1-PJ3-Pad68)") (class "Default")
      (node (ref "U1") (pin "68") (pinfunction "PJ3_68") (pintype "bidirectional"))
    )
    (net (code "94") (name "unconnected-(U1-PJ4-Pad69)") (class "Default")
      (node (ref "U1") (pin "69") (pinfunction "PJ4_69") (pintype "bidirectional"))
    )
    (net (code "95") (name "unconnected-(U1-PJ5-Pad70)") (class "Default")
      (node (ref "U1") (pin "70") (pinfunction "PJ5_70") (pintype "bidirectional"))
    )
    (net (code "96") (name "unconnected-(U1-PJ6-Pad71)") (class "Default")
      (node (ref "U1") (pin "71") (pinfunction "PJ6_71") (pintype "bidirectional"))
    )
    (net (code "97") (name "unconnected-(U1-PJ7-Pad72)") (class "Default")
      (node (ref "U1") (pin "72") (pinfunction "PJ7_72") (pintype "bidirectional"))
    )
    (net (code "98") (name "unconnected-(U1-PK0-Pad75)") (class "Default")
      (node (ref "U1") (pin "75") (pinfunction "PK0_75") (pintype "bidirectional"))
    )
    (net (code "99") (name "unconnected-(U1-PK1-Pad76)") (class "Default")
      (node (ref "U1") (pin "76") (pinfunction "PK1_76") (pintype "bidirectional"))
    )
    (net (code "100") (name "unconnected-(U1-PK2-Pad77)") (class "Default")
      (node (ref "U1") (pin "77") (pinfunction "PK2_77") (pintype "bidirectional"))
    )
    (net (code "101") (name "unconnected-(U1-PK3-Pad78)") (class "Default")
      (node (ref "U1") (pin "78") (pinfunction "PK3_78") (pintype "bidirectional"))
    )
    (net (code "102") (name "unconnected-(U1-PK4-Pad79)") (class "Default")
      (node (ref "U1") (pin "79") (pinfunction "PK4_79") (pintype "bidirectional"))
    )
    (net (code "103") (name "unconnected-(U1-PK5-Pad80)") (class "Default")
      (node (ref "U1") (pin "80") (pinfunction "PK5_80") (pintype "bidirectional"))
    )
    (net (code "104") (name "unconnected-(U1-PK6-Pad81)") (class "Default")
      (node (ref "U1") (pin "81") (pinfunction "PK6_81") (pintype "bidirectional"))
    )
    (net (code "105") (name "unconnected-(U1-PK7-Pad82)") (class "Default")
      (node (ref "U1") (pin "82") (pinfunction "PK7_82") (pintype "bidirectional"))
    )
    (net (code "106") (name "unconnected-(U1-PQ0-Pad85)") (class "Default")
      (node (ref "U1") (pin "85") (pinfunction "PQ0_85") (pintype "bidirectional"))
    )
    (net (code "107") (name "unconnected-(U1-PQ1-Pad86)") (class "Default")
      (node (ref "U1") (pin "86") (pinfunction "PQ1_86") (pintype "bidirectional"))
    )
    (net (code "108") (name "unconnected-(U1-PQ2-Pad87)") (class "Default")
      (node (ref "U1") (pin "87") (pinfunction "PQ2_87") (pintype "bidirectional"))
    )
    (net (code "109") (name "unconnected-(U1-PQ3-Pad88)") (class "Default")
      (node (ref "U1") (pin "88") (pinfunction "PQ3_88") (pintype "bidirectional"))
    )
    (net (code "110") (name "unconnected-(U1-PR0-Pad91)") (class "Default")
      (node (ref "U1") (pin "91") (pinfunction "PR0_91") (pintype "bidirectional"))
    )
    (net (code "111") (name "unconnected-(U1-PR1-Pad92)") (class "Default")
      (node (ref "U1") (pin "92") (pinfunction "PR1_92") (pintype "bidirectional"))
    )
    (net (code "112") (name "unconnected-(U4-BP-Pad7)") (class "Default")
      (node (ref "U4") (pin "7") (pinfunction "BP_7") (pintype "bidirectional"))
    )
  )
)
